# M668X.net
KiCad netlist of a schematic drawn in EAGLE
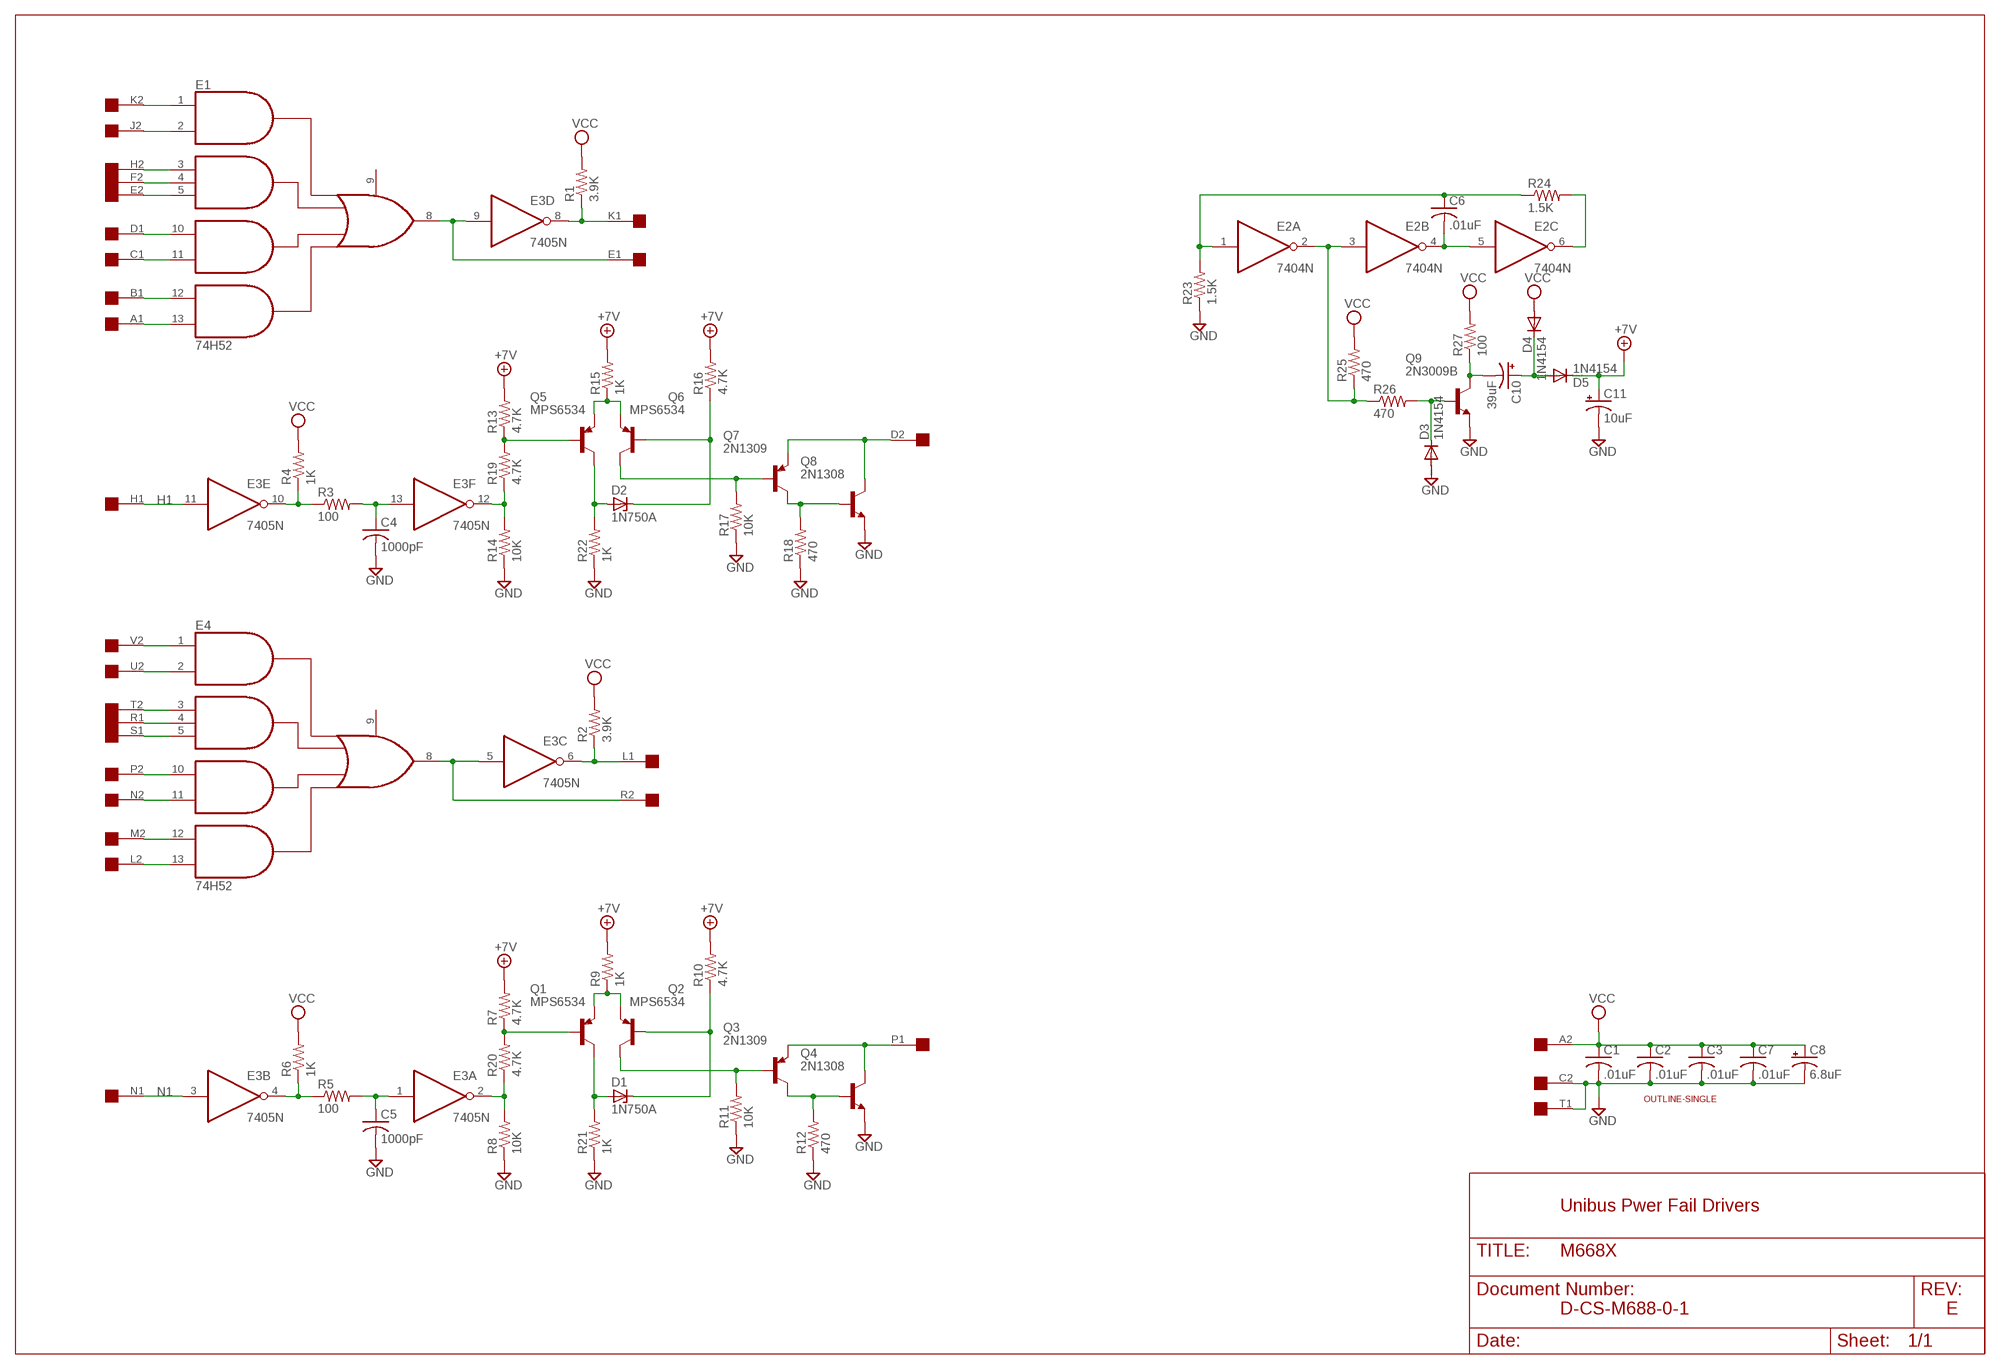
[diagram p0: schematic, sheet 1]

(export (version "E")
  (design (tool "Eeschema 10.0.6"))
  (components
    (comp (ref "C1")
      (value ".01uF")
      (footprint "eagle-import:C050-025X075")
      (libsource (lib "eagle-import") (part "C-US050-025X075"))
    )
    (comp (ref "C2")
      (value ".01uF")
      (footprint "eagle-import:C050-025X075")
      (libsource (lib "eagle-import") (part "C-US050-025X075"))
    )
    (comp (ref "C3")
      (value ".01uF")
      (footprint "eagle-import:C050-025X075")
      (libsource (lib "eagle-import") (part "C-US050-025X075"))
    )
    (comp (ref "C4")
      (value "1000pF")
      (footprint "eagle-import:C050-025X075")
      (libsource (lib "eagle-import") (part "C-US050-025X075"))
    )
    (comp (ref "C5")
      (value "1000pF")
      (footprint "eagle-import:C050-025X075")
      (libsource (lib "eagle-import") (part "C-US050-025X075"))
    )
    (comp (ref "C6")
      (value ".01uF")
      (footprint "eagle-import:C050-025X075")
      (libsource (lib "eagle-import") (part "C-US050-025X075"))
    )
    (comp (ref "C7")
      (value ".01uF")
      (footprint "eagle-import:C050-025X075")
      (libsource (lib "eagle-import") (part "C-US050-025X075"))
    )
    (comp (ref "C8")
      (value "6.8uF")
      (footprint "eagle-import:E12-8")
      (libsource (lib "eagle-import") (part "CPOL-USE20-8AXIAL"))
    )
    (comp (ref "C10")
      (value "39uF")
      (footprint "eagle-import:E12-8")
      (libsource (lib "eagle-import") (part "CPOL-USE20-8AXIAL"))
    )
    (comp (ref "C11")
      (value "10uF")
      (footprint "eagle-import:E12-8")
      (libsource (lib "eagle-import") (part "CPOL-USE20-8AXIAL"))
    )
    (comp (ref "D1")
      (value "1N750A")
      (footprint "eagle-import:DO35Z10")
      (libsource (lib "eagle-import") (part "ZENER-DIODEDO35Z10"))
    )
    (comp (ref "D2")
      (value "1N750A")
      (footprint "eagle-import:DO35Z10")
      (libsource (lib "eagle-import") (part "ZENER-DIODEDO35Z10"))
    )
    (comp (ref "D3")
      (value "1N4154")
      (footprint "eagle-import:DO35-10")
      (libsource (lib "eagle-import") (part "DIODE-DO35-10"))
    )
    (comp (ref "D4")
      (value "1N4154")
      (footprint "eagle-import:DO35-10")
      (libsource (lib "eagle-import") (part "DIODE-DO35-10"))
    )
    (comp (ref "D5")
      (value "1N4154")
      (footprint "eagle-import:DO35-10")
      (libsource (lib "eagle-import") (part "DIODE-DO35-10"))
    )
    (comp (ref "E1")
      (value "74H52")
      (footprint "eagle-import:DIL14")
      (libsource (lib "eagle-import") (part "7452H"))
    )
    (comp (ref "E2")
      (value "7404N")
      (footprint "eagle-import:DIL14")
      (libsource (lib "eagle-import") (part "7404N"))
    )
    (comp (ref "E3")
      (value "7405N")
      (footprint "eagle-import:DIL14")
      (libsource (lib "eagle-import") (part "7405N"))
    )
    (comp (ref "E4")
      (value "74H52")
      (footprint "eagle-import:DIL14")
      (libsource (lib "eagle-import") (part "7452H"))
    )
    (comp (ref "Q1")
      (value "MPS6534")
      (footprint "eagle-import:TO5")
      (libsource (lib "eagle-import") (part "-PNP-TO5"))
    )
    (comp (ref "Q2")
      (value "MPS6534")
      (footprint "eagle-import:TO5")
      (libsource (lib "eagle-import") (part "-PNP-TO5"))
    )
    (comp (ref "Q3")
      (value "2N1309")
      (footprint "eagle-import:TO5")
      (libsource (lib "eagle-import") (part "-PNP-TO5"))
    )
    (comp (ref "Q4")
      (value "2N1308")
      (footprint "eagle-import:TO5")
      (libsource (lib "eagle-import") (part "-NPN-TO5"))
    )
    (comp (ref "Q5")
      (value "MPS6534")
      (footprint "eagle-import:TO5")
      (libsource (lib "eagle-import") (part "-PNP-TO5"))
    )
    (comp (ref "Q6")
      (value "MPS6534")
      (footprint "eagle-import:TO5")
      (libsource (lib "eagle-import") (part "-PNP-TO5"))
    )
    (comp (ref "Q7")
      (value "2N1309")
      (footprint "eagle-import:TO5")
      (libsource (lib "eagle-import") (part "-PNP-TO5"))
    )
    (comp (ref "Q8")
      (value "2N1308")
      (footprint "eagle-import:TO5")
      (libsource (lib "eagle-import") (part "-NPN-TO5"))
    )
    (comp (ref "Q9")
      (value "2N3009B")
      (footprint "eagle-import:TO5")
      (libsource (lib "eagle-import") (part "-NPN-TO5"))
    )
    (comp (ref "R1")
      (value "3.9K")
      (footprint "eagle-import:0207_10")
      (libsource (lib "eagle-import") (part "R-US_0207/10"))
    )
    (comp (ref "R2")
      (value "3.9K")
      (footprint "eagle-import:0207_10")
      (libsource (lib "eagle-import") (part "R-US_0207/10"))
    )
    (comp (ref "R3")
      (value "100")
      (footprint "eagle-import:0207_10")
      (libsource (lib "eagle-import") (part "R-US_0207/10"))
    )
    (comp (ref "R4")
      (value "1K")
      (footprint "eagle-import:0207_10")
      (libsource (lib "eagle-import") (part "R-US_0207/10"))
    )
    (comp (ref "R5")
      (value "100")
      (footprint "eagle-import:0207_10")
      (libsource (lib "eagle-import") (part "R-US_0207/10"))
    )
    (comp (ref "R6")
      (value "1K")
      (footprint "eagle-import:0207_10")
      (libsource (lib "eagle-import") (part "R-US_0207/10"))
    )
    (comp (ref "R7")
      (value "4.7K")
      (footprint "eagle-import:0207_10")
      (libsource (lib "eagle-import") (part "R-US_0207/10"))
    )
    (comp (ref "R8")
      (value "10K")
      (footprint "eagle-import:0207_10")
      (libsource (lib "eagle-import") (part "R-US_0207/10"))
    )
    (comp (ref "R9")
      (value "1K")
      (footprint "eagle-import:0207_10")
      (libsource (lib "eagle-import") (part "R-US_0207/10"))
    )
    (comp (ref "R10")
      (value "4.7K")
      (footprint "eagle-import:0207_10")
      (libsource (lib "eagle-import") (part "R-US_0207/10"))
    )
    (comp (ref "R11")
      (value "10K")
      (footprint "eagle-import:0207_10")
      (libsource (lib "eagle-import") (part "R-US_0207/10"))
    )
    (comp (ref "R12")
      (value "470")
      (footprint "eagle-import:0207_10")
      (libsource (lib "eagle-import") (part "R-US_0207/10"))
    )
    (comp (ref "R13")
      (value "4.7K")
      (footprint "eagle-import:0207_10")
      (libsource (lib "eagle-import") (part "R-US_0207/10"))
    )
    (comp (ref "R14")
      (value "10K")
      (footprint "eagle-import:0207_10")
      (libsource (lib "eagle-import") (part "R-US_0207/10"))
    )
    (comp (ref "R15")
      (value "1K")
      (footprint "eagle-import:0207_10")
      (libsource (lib "eagle-import") (part "R-US_0207/10"))
    )
    (comp (ref "R16")
      (value "4.7K")
      (footprint "eagle-import:0207_10")
      (libsource (lib "eagle-import") (part "R-US_0207/10"))
    )
    (comp (ref "R17")
      (value "10K")
      (footprint "eagle-import:0207_10")
      (libsource (lib "eagle-import") (part "R-US_0207/10"))
    )
    (comp (ref "R18")
      (value "470")
      (footprint "eagle-import:0207_10")
      (libsource (lib "eagle-import") (part "R-US_0207/10"))
    )
    (comp (ref "R19")
      (value "4.7K")
      (footprint "eagle-import:0207_10")
      (libsource (lib "eagle-import") (part "R-US_0207/10"))
    )
    (comp (ref "R20")
      (value "4.7K")
      (footprint "eagle-import:0207_10")
      (libsource (lib "eagle-import") (part "R-US_0207/10"))
    )
    (comp (ref "R21")
      (value "1K")
      (footprint "eagle-import:0207_10")
      (libsource (lib "eagle-import") (part "R-US_0207/10"))
    )
    (comp (ref "R22")
      (value "1K")
      (footprint "eagle-import:0207_10")
      (libsource (lib "eagle-import") (part "R-US_0207/10"))
    )
    (comp (ref "R23")
      (value "1.5K")
      (footprint "eagle-import:0207_10")
      (libsource (lib "eagle-import") (part "R-US_0207/10"))
    )
    (comp (ref "R24")
      (value "1.5K")
      (footprint "eagle-import:0207_10")
      (libsource (lib "eagle-import") (part "R-US_0207/10"))
    )
    (comp (ref "R25")
      (value "470")
      (footprint "eagle-import:0207_10")
      (libsource (lib "eagle-import") (part "R-US_0207/10"))
    )
    (comp (ref "R26")
      (value "470")
      (footprint "eagle-import:0207_10")
      (libsource (lib "eagle-import") (part "R-US_0207/10"))
    )
    (comp (ref "R27")
      (value "100")
      (footprint "eagle-import:0207_10")
      (libsource (lib "eagle-import") (part "R-US_0207/10"))
    )
    (comp (ref "U$1")
      (value "OUTLINE-SINGLE")
      (footprint "eagle-import:SINGLE")
      (libsource (lib "eagle-import") (part "OUTLINE-SINGLE"))
    )
    (comp (ref "U$2")
      (value "SINGLE")
      (footprint "eagle-import:EDGE-CON2")
      (libsource (lib "eagle-import") (part "SINGLE"))
    )
  )
  (nets
    (net (code "1") (name "+7V") (class "Default")
      (node (ref "C11") (pin "+") (pinfunction "+_+") (pintype "passive"))
      (node (ref "D5") (pin "C") (pinfunction "C_C") (pintype "passive"))
      (node (ref "R10") (pin "2") (pinfunction "2_2") (pintype "passive"))
      (node (ref "R13") (pin "2") (pinfunction "2_2") (pintype "passive"))
      (node (ref "R15") (pin "2") (pinfunction "2_2") (pintype "passive"))
      (node (ref "R16") (pin "2") (pinfunction "2_2") (pintype "passive"))
      (node (ref "R7") (pin "2") (pinfunction "2_2") (pintype "passive"))
      (node (ref "R9") (pin "2") (pinfunction "2_2") (pintype "passive"))
    )
    (net (code "2") (name "/H1") (class "Default")
      (node (ref "E3") (pin "11") (pinfunction "I_11") (pintype "input"))
      (node (ref "U$2") (pin "H1") (pinfunction "1_H1") (pintype "bidirectional"))
    )
    (net (code "3") (name "/N1") (class "Default")
      (node (ref "E3") (pin "3") (pinfunction "I_3") (pintype "input"))
      (node (ref "U$2") (pin "N1") (pinfunction "1_N1") (pintype "bidirectional"))
    )
    (net (code "4") (name "GND") (class "Default")
      (node (ref "C1") (pin "2") (pinfunction "2_2") (pintype "passive"))
      (node (ref "C11") (pin "-") (pinfunction "-_-") (pintype "passive"))
      (node (ref "C2") (pin "2") (pinfunction "2_2") (pintype "passive"))
      (node (ref "C3") (pin "2") (pinfunction "2_2") (pintype "passive"))
      (node (ref "C4") (pin "2") (pinfunction "2_2") (pintype "passive"))
      (node (ref "C5") (pin "2") (pinfunction "2_2") (pintype "passive"))
      (node (ref "C7") (pin "2") (pinfunction "2_2") (pintype "passive"))
      (node (ref "C8") (pin "-") (pinfunction "-_-") (pintype "passive"))
      (node (ref "D3") (pin "A") (pinfunction "A_A") (pintype "passive"))
      (node (ref "Q4") (pin "1") (pinfunction "E_1") (pintype "passive"))
      (node (ref "Q8") (pin "1") (pinfunction "E_1") (pintype "passive"))
      (node (ref "Q9") (pin "1") (pinfunction "E_1") (pintype "passive"))
      (node (ref "R11") (pin "1") (pinfunction "1_1") (pintype "passive"))
      (node (ref "R12") (pin "1") (pinfunction "1_1") (pintype "passive"))
      (node (ref "R14") (pin "1") (pinfunction "1_1") (pintype "passive"))
      (node (ref "R17") (pin "1") (pinfunction "1_1") (pintype "passive"))
      (node (ref "R18") (pin "1") (pinfunction "1_1") (pintype "passive"))
      (node (ref "R21") (pin "1") (pinfunction "1_1") (pintype "passive"))
      (node (ref "R22") (pin "1") (pinfunction "1_1") (pintype "passive"))
      (node (ref "R23") (pin "1") (pinfunction "1_1") (pintype "passive"))
      (node (ref "R8") (pin "1") (pinfunction "1_1") (pintype "passive"))
      (node (ref "U$2") (pin "C2") (pinfunction "1_C2") (pintype "bidirectional"))
      (node (ref "U$2") (pin "T1") (pinfunction "1_T1") (pintype "bidirectional"))
    )
    (net (code "5") (name "Net-(C10-Pad+)") (class "Default")
      (node (ref "C10") (pin "+") (pinfunction "+_+") (pintype "passive"))
      (node (ref "D4") (pin "C") (pinfunction "C_C") (pintype "passive"))
      (node (ref "D5") (pin "A") (pinfunction "A_A") (pintype "passive"))
    )
    (net (code "6") (name "Net-(E1A-I1)") (class "Default")
      (node (ref "E1") (pin "1") (pinfunction "I1_1") (pintype "input"))
      (node (ref "U$2") (pin "K2") (pinfunction "1_K2") (pintype "bidirectional"))
    )
    (net (code "7") (name "Net-(E1A-I2)") (class "Default")
      (node (ref "E1") (pin "2") (pinfunction "I2_2") (pintype "input"))
      (node (ref "U$2") (pin "J2") (pinfunction "1_J2") (pintype "bidirectional"))
    )
    (net (code "8") (name "Net-(E1A-I3)") (class "Default")
      (node (ref "E1") (pin "3") (pinfunction "I3_3") (pintype "input"))
      (node (ref "U$2") (pin "H2") (pinfunction "1_H2") (pintype "bidirectional"))
    )
    (net (code "9") (name "Net-(E1A-I4)") (class "Default")
      (node (ref "E1") (pin "4") (pinfunction "I4_4") (pintype "input"))
      (node (ref "U$2") (pin "F2") (pinfunction "1_F2") (pintype "bidirectional"))
    )
    (net (code "10") (name "Net-(E1A-I5)") (class "Default")
      (node (ref "E1") (pin "5") (pinfunction "I5_5") (pintype "input"))
      (node (ref "U$2") (pin "E2") (pinfunction "1_E2") (pintype "bidirectional"))
    )
    (net (code "11") (name "Net-(E1A-I10)") (class "Default")
      (node (ref "E1") (pin "10") (pinfunction "I10_10") (pintype "input"))
      (node (ref "U$2") (pin "D1") (pinfunction "1_D1") (pintype "bidirectional"))
    )
    (net (code "12") (name "Net-(E1A-I11)") (class "Default")
      (node (ref "E1") (pin "11") (pinfunction "I11_11") (pintype "input"))
      (node (ref "U$2") (pin "C1") (pinfunction "1_C1") (pintype "bidirectional"))
    )
    (net (code "13") (name "Net-(E1A-I12)") (class "Default")
      (node (ref "E1") (pin "12") (pinfunction "I12_12") (pintype "input"))
      (node (ref "U$2") (pin "B1") (pinfunction "1_B1") (pintype "bidirectional"))
    )
    (net (code "14") (name "Net-(E1A-I13)") (class "Default")
      (node (ref "E1") (pin "13") (pinfunction "I13_13") (pintype "input"))
      (node (ref "U$2") (pin "A1") (pinfunction "1_A1") (pintype "bidirectional"))
    )
    (net (code "15") (name "Net-(E1A-O8)") (class "Default")
      (node (ref "E1") (pin "8") (pinfunction "O8_8") (pintype "output"))
      (node (ref "E3") (pin "9") (pinfunction "I_9") (pintype "input"))
      (node (ref "U$2") (pin "E1") (pinfunction "1_E1") (pintype "bidirectional"))
    )
    (net (code "16") (name "Net-(E2A-I)") (class "Default")
      (node (ref "C6") (pin "1") (pinfunction "1_1") (pintype "passive"))
      (node (ref "E2") (pin "1") (pinfunction "I_1") (pintype "input"))
      (node (ref "R23") (pin "2") (pinfunction "2_2") (pintype "passive"))
      (node (ref "R24") (pin "1") (pinfunction "1_1") (pintype "passive"))
    )
    (net (code "17") (name "Net-(E2A-O)") (class "Default")
      (node (ref "E2") (pin "2") (pinfunction "O_2") (pintype "output"))
      (node (ref "E2") (pin "3") (pinfunction "I_3") (pintype "input"))
      (node (ref "R25") (pin "1") (pinfunction "1_1") (pintype "passive"))
      (node (ref "R26") (pin "1") (pinfunction "1_1") (pintype "passive"))
    )
    (net (code "18") (name "Net-(E2B-O)") (class "Default")
      (node (ref "C6") (pin "2") (pinfunction "2_2") (pintype "passive"))
      (node (ref "E2") (pin "4") (pinfunction "O_4") (pintype "output"))
      (node (ref "E2") (pin "5") (pinfunction "I_5") (pintype "input"))
    )
    (net (code "19") (name "Net-(E2C-O)") (class "Default")
      (node (ref "E2") (pin "6") (pinfunction "O_6") (pintype "output"))
      (node (ref "R24") (pin "2") (pinfunction "2_2") (pintype "passive"))
    )
    (net (code "20") (name "Net-(E3A-I)") (class "Default")
      (node (ref "C5") (pin "1") (pinfunction "1_1") (pintype "passive"))
      (node (ref "E3") (pin "1") (pinfunction "I_1") (pintype "input"))
      (node (ref "R5") (pin "2") (pinfunction "2_2") (pintype "passive"))
    )
    (net (code "21") (name "Net-(E3A-O)") (class "Default")
      (node (ref "E3") (pin "2") (pinfunction "O_2") (pintype "open_collector"))
      (node (ref "R20") (pin "1") (pinfunction "1_1") (pintype "passive"))
      (node (ref "R8") (pin "2") (pinfunction "2_2") (pintype "passive"))
    )
    (net (code "22") (name "Net-(E3B-O)") (class "Default")
      (node (ref "E3") (pin "4") (pinfunction "O_4") (pintype "open_collector"))
      (node (ref "R5") (pin "1") (pinfunction "1_1") (pintype "passive"))
      (node (ref "R6") (pin "1") (pinfunction "1_1") (pintype "passive"))
    )
    (net (code "23") (name "Net-(E3C-I)") (class "Default")
      (node (ref "E3") (pin "5") (pinfunction "I_5") (pintype "input"))
      (node (ref "E4") (pin "8") (pinfunction "O8_8") (pintype "output"))
      (node (ref "U$2") (pin "R2") (pinfunction "1_R2") (pintype "bidirectional"))
    )
    (net (code "24") (name "Net-(E3C-O)") (class "Default")
      (node (ref "E3") (pin "6") (pinfunction "O_6") (pintype "open_collector"))
      (node (ref "R2") (pin "1") (pinfunction "1_1") (pintype "passive"))
      (node (ref "U$2") (pin "L1") (pinfunction "1_L1") (pintype "bidirectional"))
    )
    (net (code "25") (name "Net-(E3D-O)") (class "Default")
      (node (ref "E3") (pin "8") (pinfunction "O_8") (pintype "open_collector"))
      (node (ref "R1") (pin "1") (pinfunction "1_1") (pintype "passive"))
      (node (ref "U$2") (pin "K1") (pinfunction "1_K1") (pintype "bidirectional"))
    )
    (net (code "26") (name "Net-(E3E-O)") (class "Default")
      (node (ref "E3") (pin "10") (pinfunction "O_10") (pintype "open_collector"))
      (node (ref "R3") (pin "1") (pinfunction "1_1") (pintype "passive"))
      (node (ref "R4") (pin "1") (pinfunction "1_1") (pintype "passive"))
    )
    (net (code "27") (name "Net-(E3F-I)") (class "Default")
      (node (ref "C4") (pin "1") (pinfunction "1_1") (pintype "passive"))
      (node (ref "E3") (pin "13") (pinfunction "I_13") (pintype "input"))
      (node (ref "R3") (pin "2") (pinfunction "2_2") (pintype "passive"))
    )
    (net (code "28") (name "Net-(E3F-O)") (class "Default")
      (node (ref "E3") (pin "12") (pinfunction "O_12") (pintype "open_collector"))
      (node (ref "R14") (pin "2") (pinfunction "2_2") (pintype "passive"))
      (node (ref "R19") (pin "1") (pinfunction "1_1") (pintype "passive"))
    )
    (net (code "29") (name "Net-(E4A-I1)") (class "Default")
      (node (ref "E4") (pin "1") (pinfunction "I1_1") (pintype "input"))
      (node (ref "U$2") (pin "V2") (pinfunction "1_V2") (pintype "bidirectional"))
    )
    (net (code "30") (name "Net-(E4A-I2)") (class "Default")
      (node (ref "E4") (pin "2") (pinfunction "I2_2") (pintype "input"))
      (node (ref "U$2") (pin "U2") (pinfunction "1_U2") (pintype "bidirectional"))
    )
    (net (code "31") (name "Net-(E4A-I3)") (class "Default")
      (node (ref "E4") (pin "3") (pinfunction "I3_3") (pintype "input"))
      (node (ref "U$2") (pin "T2") (pinfunction "1_T2") (pintype "bidirectional"))
    )
    (net (code "32") (name "Net-(E4A-I4)") (class "Default")
      (node (ref "E4") (pin "4") (pinfunction "I4_4") (pintype "input"))
      (node (ref "U$2") (pin "R1") (pinfunction "1_R1") (pintype "bidirectional"))
    )
    (net (code "33") (name "Net-(E4A-I5)") (class "Default")
      (node (ref "E4") (pin "5") (pinfunction "I5_5") (pintype "input"))
      (node (ref "U$2") (pin "S1") (pinfunction "1_S1") (pintype "bidirectional"))
    )
    (net (code "34") (name "Net-(E4A-I10)") (class "Default")
      (node (ref "E4") (pin "10") (pinfunction "I10_10") (pintype "input"))
      (node (ref "U$2") (pin "P2") (pinfunction "1_P2") (pintype "bidirectional"))
    )
    (net (code "35") (name "Net-(E4A-I11)") (class "Default")
      (node (ref "E4") (pin "11") (pinfunction "I11_11") (pintype "input"))
      (node (ref "U$2") (pin "N2") (pinfunction "1_N2") (pintype "bidirectional"))
    )
    (net (code "36") (name "Net-(E4A-I12)") (class "Default")
      (node (ref "E4") (pin "12") (pinfunction "I12_12") (pintype "input"))
      (node (ref "U$2") (pin "M2") (pinfunction "1_M2") (pintype "bidirectional"))
    )
    (net (code "37") (name "Net-(E4A-I13)") (class "Default")
      (node (ref "E4") (pin "13") (pinfunction "I13_13") (pintype "input"))
      (node (ref "U$2") (pin "L2") (pinfunction "1_L2") (pintype "bidirectional"))
    )
    (net (code "38") (name "Net-(Q1-B)") (class "Default")
      (node (ref "Q1") (pin "2") (pinfunction "B_2") (pintype "passive"))
      (node (ref "R20") (pin "2") (pinfunction "2_2") (pintype "passive"))
      (node (ref "R7") (pin "1") (pinfunction "1_1") (pintype "passive"))
    )
    (net (code "39") (name "Net-(Q1-C)") (class "Default")
      (node (ref "D1") (pin "A") (pinfunction "A_A") (pintype "passive"))
      (node (ref "Q1") (pin "3") (pinfunction "C_3") (pintype "passive"))
      (node (ref "R21") (pin "2") (pinfunction "2_2") (pintype "passive"))
    )
    (net (code "40") (name "Net-(Q1-E)") (class "Default")
      (node (ref "Q1") (pin "1") (pinfunction "E_1") (pintype "passive"))
      (node (ref "Q2") (pin "1") (pinfunction "E_1") (pintype "passive"))
      (node (ref "R9") (pin "1") (pinfunction "1_1") (pintype "passive"))
    )
    (net (code "41") (name "Net-(Q2-B)") (class "Default")
      (node (ref "D1") (pin "C") (pinfunction "C_C") (pintype "passive"))
      (node (ref "Q2") (pin "2") (pinfunction "B_2") (pintype "passive"))
      (node (ref "R10") (pin "1") (pinfunction "1_1") (pintype "passive"))
    )
    (net (code "42") (name "Net-(Q2-C)") (class "Default")
      (node (ref "Q2") (pin "3") (pinfunction "C_3") (pintype "passive"))
      (node (ref "Q3") (pin "2") (pinfunction "B_2") (pintype "passive"))
      (node (ref "R11") (pin "2") (pinfunction "2_2") (pintype "passive"))
    )
    (net (code "43") (name "Net-(Q3-C)") (class "Default")
      (node (ref "Q3") (pin "3") (pinfunction "C_3") (pintype "passive"))
      (node (ref "Q4") (pin "2") (pinfunction "B_2") (pintype "passive"))
      (node (ref "R12") (pin "2") (pinfunction "2_2") (pintype "passive"))
    )
    (net (code "44") (name "Net-(Q3-E)") (class "Default")
      (node (ref "Q3") (pin "1") (pinfunction "E_1") (pintype "passive"))
      (node (ref "Q4") (pin "3") (pinfunction "C_3") (pintype "passive"))
      (node (ref "U$2") (pin "P1") (pinfunction "1_P1") (pintype "bidirectional"))
    )
    (net (code "45") (name "Net-(Q5-B)") (class "Default")
      (node (ref "Q5") (pin "2") (pinfunction "B_2") (pintype "passive"))
      (node (ref "R13") (pin "1") (pinfunction "1_1") (pintype "passive"))
      (node (ref "R19") (pin "2") (pinfunction "2_2") (pintype "passive"))
    )
    (net (code "46") (name "Net-(Q5-C)") (class "Default")
      (node (ref "D2") (pin "A") (pinfunction "A_A") (pintype "passive"))
      (node (ref "Q5") (pin "3") (pinfunction "C_3") (pintype "passive"))
      (node (ref "R22") (pin "2") (pinfunction "2_2") (pintype "passive"))
    )
    (net (code "47") (name "Net-(Q5-E)") (class "Default")
      (node (ref "Q5") (pin "1") (pinfunction "E_1") (pintype "passive"))
      (node (ref "Q6") (pin "1") (pinfunction "E_1") (pintype "passive"))
      (node (ref "R15") (pin "1") (pinfunction "1_1") (pintype "passive"))
    )
    (net (code "48") (name "Net-(Q6-B)") (class "Default")
      (node (ref "D2") (pin "C") (pinfunction "C_C") (pintype "passive"))
      (node (ref "Q6") (pin "2") (pinfunction "B_2") (pintype "passive"))
      (node (ref "R16") (pin "1") (pinfunction "1_1") (pintype "passive"))
    )
    (net (code "49") (name "Net-(Q6-C)") (class "Default")
      (node (ref "Q6") (pin "3") (pinfunction "C_3") (pintype "passive"))
      (node (ref "Q7") (pin "2") (pinfunction "B_2") (pintype "passive"))
      (node (ref "R17") (pin "2") (pinfunction "2_2") (pintype "passive"))
    )
    (net (code "50") (name "Net-(Q7-C)") (class "Default")
      (node (ref "Q7") (pin "3") (pinfunction "C_3") (pintype "passive"))
      (node (ref "Q8") (pin "2") (pinfunction "B_2") (pintype "passive"))
      (node (ref "R18") (pin "2") (pinfunction "2_2") (pintype "passive"))
    )
    (net (code "51") (name "Net-(Q7-E)") (class "Default")
      (node (ref "Q7") (pin "1") (pinfunction "E_1") (pintype "passive"))
      (node (ref "Q8") (pin "3") (pinfunction "C_3") (pintype "passive"))
      (node (ref "U$2") (pin "D2") (pinfunction "1_D2") (pintype "bidirectional"))
    )
    (net (code "52") (name "Net-(Q9-B)") (class "Default")
      (node (ref "D3") (pin "C") (pinfunction "C_C") (pintype "passive"))
      (node (ref "Q9") (pin "2") (pinfunction "B_2") (pintype "passive"))
      (node (ref "R26") (pin "2") (pinfunction "2_2") (pintype "passive"))
    )
    (net (code "53") (name "Net-(Q9-C)") (class "Default")
      (node (ref "C10") (pin "-") (pinfunction "-_-") (pintype "passive"))
      (node (ref "Q9") (pin "3") (pinfunction "C_3") (pintype "passive"))
      (node (ref "R27") (pin "1") (pinfunction "1_1") (pintype "passive"))
    )
    (net (code "54") (name "VCC") (class "Default")
      (node (ref "C1") (pin "1") (pinfunction "1_1") (pintype "passive"))
      (node (ref "C2") (pin "1") (pinfunction "1_1") (pintype "passive"))
      (node (ref "C3") (pin "1") (pinfunction "1_1") (pintype "passive"))
      (node (ref "C7") (pin "1") (pinfunction "1_1") (pintype "passive"))
      (node (ref "C8") (pin "+") (pinfunction "+_+") (pintype "passive"))
      (node (ref "D4") (pin "A") (pinfunction "A_A") (pintype "passive"))
      (node (ref "R1") (pin "2") (pinfunction "2_2") (pintype "passive"))
      (node (ref "R2") (pin "2") (pinfunction "2_2") (pintype "passive"))
      (node (ref "R25") (pin "2") (pinfunction "2_2") (pintype "passive"))
      (node (ref "R27") (pin "2") (pinfunction "2_2") (pintype "passive"))
      (node (ref "R4") (pin "2") (pinfunction "2_2") (pintype "passive"))
      (node (ref "R6") (pin "2") (pinfunction "2_2") (pintype "passive"))
      (node (ref "U$2") (pin "A2") (pinfunction "1_A2") (pintype "bidirectional"))
    )
    (net (code "55") (name "unconnected-(E1A-I9-Pad9)") (class "Default")
      (node (ref "E1") (pin "9") (pinfunction "I9_9") (pintype "passive"))
    )
    (net (code "56") (name "unconnected-(E4A-I9-Pad9)") (class "Default")
      (node (ref "E4") (pin "9") (pinfunction "I9_9") (pintype "passive"))
    )
  )
)
